# RGB_LED_1_4.net
KiCad netlist of a schematic drawn in EAGLE
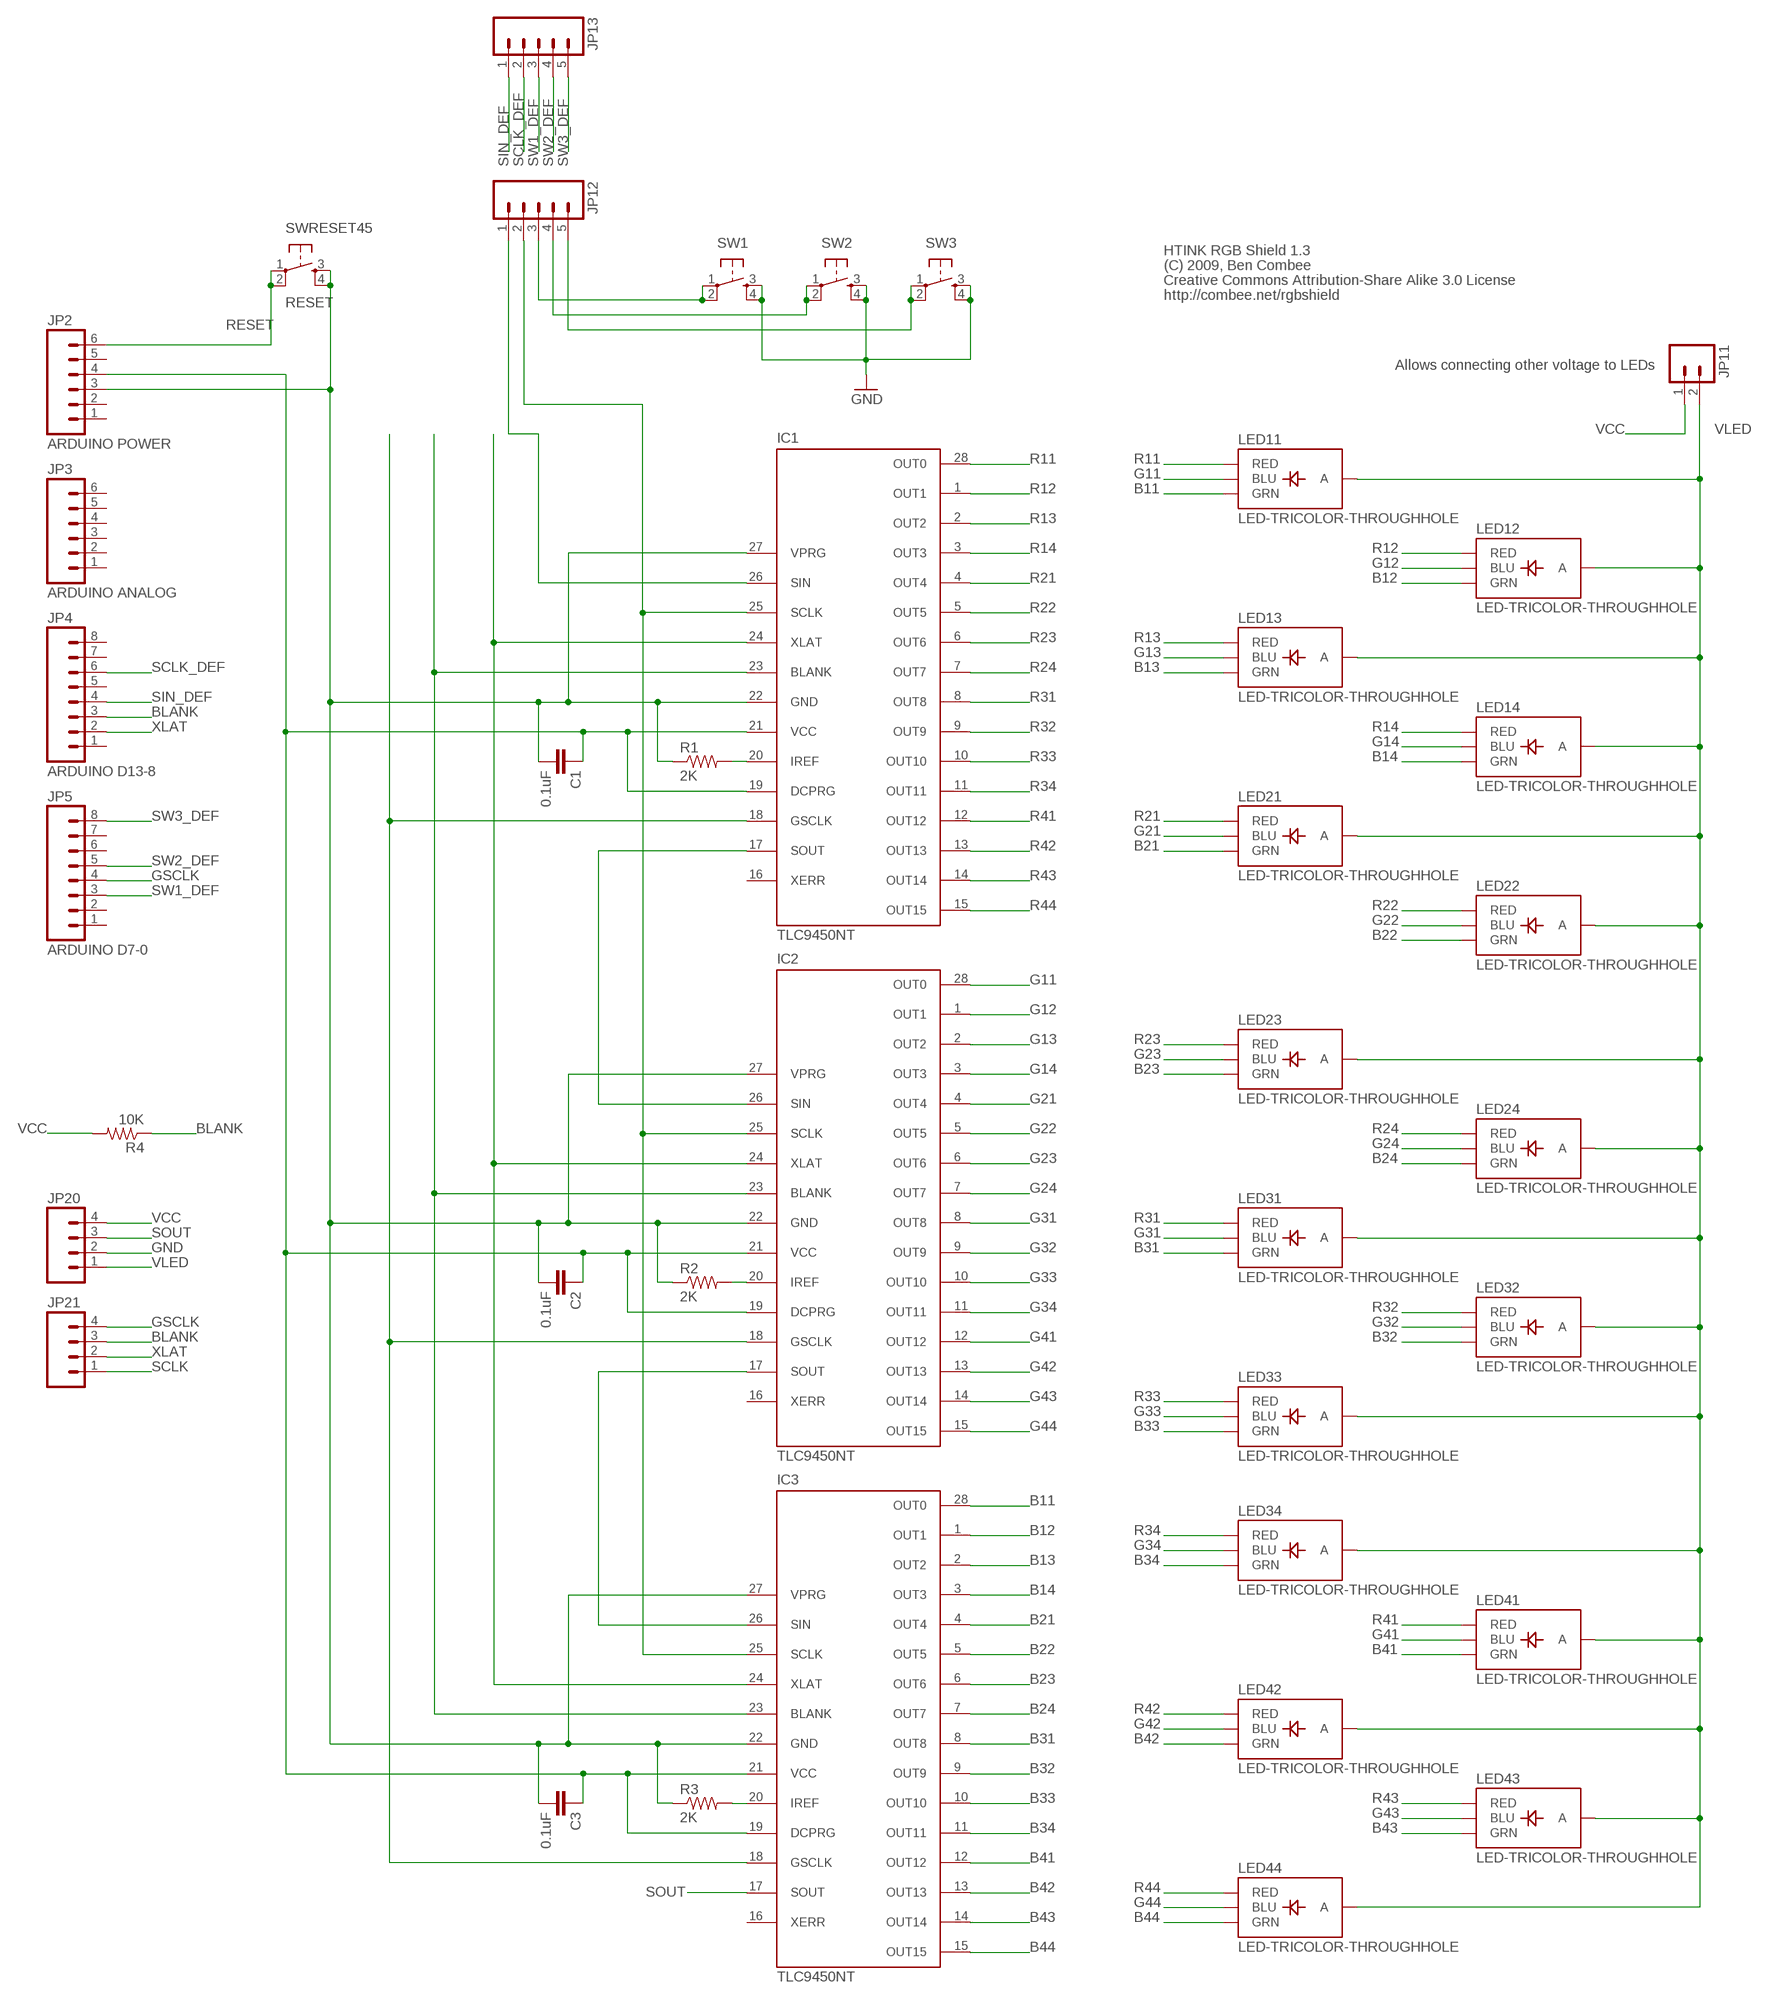
[diagram p0: schematic, sheet 1]

(export (version "E")
  (design (tool "Eeschema 10.0.6"))
  (components
    (comp (ref "C1")
      (value "0.1uF")
      (footprint "eagle-import:CAP-PTH-SMALL")
      (libsource (lib "eagle-import") (part "CAPPTH"))
    )
    (comp (ref "C2")
      (value "0.1uF")
      (footprint "eagle-import:CAP-PTH-SMALL")
      (libsource (lib "eagle-import") (part "CAPPTH"))
    )
    (comp (ref "C3")
      (value "0.1uF")
      (footprint "eagle-import:CAP-PTH-SMALL")
      (libsource (lib "eagle-import") (part "CAPPTH"))
    )
    (comp (ref "IC1")
      (value "TLC9450NT")
      (footprint "eagle-import:DIL28-3")
      (libsource (lib "eagle-import") (part "TLC9450NT"))
    )
    (comp (ref "IC2")
      (value "TLC9450NT")
      (footprint "eagle-import:DIL28-3")
      (libsource (lib "eagle-import") (part "TLC9450NT"))
    )
    (comp (ref "IC3")
      (value "TLC9450NT")
      (footprint "eagle-import:DIL28-3")
      (libsource (lib "eagle-import") (part "TLC9450NT"))
    )
    (comp (ref "JP2")
      (value "ARDUINO POWER")
      (footprint "eagle-import:1X06_LOCK")
      (libsource (lib "eagle-import") (part "M06LOCK"))
    )
    (comp (ref "JP3")
      (value "ARDUINO ANALOG")
      (footprint "eagle-import:1X06_LOCK")
      (libsource (lib "eagle-import") (part "M06LOCK"))
    )
    (comp (ref "JP4")
      (value "ARDUINO D13-8")
      (footprint "eagle-import:1X08_LOCK")
      (libsource (lib "eagle-import") (part "M08LOCK"))
    )
    (comp (ref "JP5")
      (value "ARDUINO D7-0")
      (footprint "eagle-import:1X08_LOCK")
      (libsource (lib "eagle-import") (part "M08LOCK"))
    )
    (comp (ref "JP11")
      (value "M02LOCK")
      (footprint "eagle-import:1X02_LOCK")
      (libsource (lib "eagle-import") (part "M02LOCK"))
    )
    (comp (ref "JP12")
      (value "M05LOCK")
      (footprint "eagle-import:1X05_LOCK")
      (libsource (lib "eagle-import") (part "M05LOCK"))
    )
    (comp (ref "JP13")
      (value "M05LOCK")
      (footprint "eagle-import:1X05_LOCK")
      (libsource (lib "eagle-import") (part "M05LOCK"))
    )
    (comp (ref "JP20")
      (value "M04LOCK")
      (footprint "eagle-import:1X04_LOCK")
      (libsource (lib "eagle-import") (part "M04LOCK"))
    )
    (comp (ref "JP21")
      (value "M04LOCK")
      (footprint "eagle-import:1X04_LOCK")
      (libsource (lib "eagle-import") (part "M04LOCK"))
    )
    (comp (ref "LED11")
      (value "LED-TRICOLOR-THROUGHHOLE")
      (footprint "eagle-import:LED-TRICOLOR-THROUGHHOLE")
      (libsource (lib "eagle-import") (part "LED-TRICOLOR-THROUGHHOLE"))
    )
    (comp (ref "LED12")
      (value "LED-TRICOLOR-THROUGHHOLE")
      (footprint "eagle-import:LED-TRICOLOR-THROUGHHOLE")
      (libsource (lib "eagle-import") (part "LED-TRICOLOR-THROUGHHOLE"))
    )
    (comp (ref "LED13")
      (value "LED-TRICOLOR-THROUGHHOLE")
      (footprint "eagle-import:LED-TRICOLOR-THROUGHHOLE")
      (libsource (lib "eagle-import") (part "LED-TRICOLOR-THROUGHHOLE"))
    )
    (comp (ref "LED14")
      (value "LED-TRICOLOR-THROUGHHOLE")
      (footprint "eagle-import:LED-TRICOLOR-THROUGHHOLE")
      (libsource (lib "eagle-import") (part "LED-TRICOLOR-THROUGHHOLE"))
    )
    (comp (ref "LED21")
      (value "LED-TRICOLOR-THROUGHHOLE")
      (footprint "eagle-import:LED-TRICOLOR-THROUGHHOLE")
      (libsource (lib "eagle-import") (part "LED-TRICOLOR-THROUGHHOLE"))
    )
    (comp (ref "LED22")
      (value "LED-TRICOLOR-THROUGHHOLE")
      (footprint "eagle-import:LED-TRICOLOR-THROUGHHOLE")
      (libsource (lib "eagle-import") (part "LED-TRICOLOR-THROUGHHOLE"))
    )
    (comp (ref "LED23")
      (value "LED-TRICOLOR-THROUGHHOLE")
      (footprint "eagle-import:LED-TRICOLOR-THROUGHHOLE")
      (libsource (lib "eagle-import") (part "LED-TRICOLOR-THROUGHHOLE"))
    )
    (comp (ref "LED24")
      (value "LED-TRICOLOR-THROUGHHOLE")
      (footprint "eagle-import:LED-TRICOLOR-THROUGHHOLE")
      (libsource (lib "eagle-import") (part "LED-TRICOLOR-THROUGHHOLE"))
    )
    (comp (ref "LED31")
      (value "LED-TRICOLOR-THROUGHHOLE")
      (footprint "eagle-import:LED-TRICOLOR-THROUGHHOLE")
      (libsource (lib "eagle-import") (part "LED-TRICOLOR-THROUGHHOLE"))
    )
    (comp (ref "LED32")
      (value "LED-TRICOLOR-THROUGHHOLE")
      (footprint "eagle-import:LED-TRICOLOR-THROUGHHOLE")
      (libsource (lib "eagle-import") (part "LED-TRICOLOR-THROUGHHOLE"))
    )
    (comp (ref "LED33")
      (value "LED-TRICOLOR-THROUGHHOLE")
      (footprint "eagle-import:LED-TRICOLOR-THROUGHHOLE")
      (libsource (lib "eagle-import") (part "LED-TRICOLOR-THROUGHHOLE"))
    )
    (comp (ref "LED34")
      (value "LED-TRICOLOR-THROUGHHOLE")
      (footprint "eagle-import:LED-TRICOLOR-THROUGHHOLE")
      (libsource (lib "eagle-import") (part "LED-TRICOLOR-THROUGHHOLE"))
    )
    (comp (ref "LED41")
      (value "LED-TRICOLOR-THROUGHHOLE")
      (footprint "eagle-import:LED-TRICOLOR-THROUGHHOLE")
      (libsource (lib "eagle-import") (part "LED-TRICOLOR-THROUGHHOLE"))
    )
    (comp (ref "LED42")
      (value "LED-TRICOLOR-THROUGHHOLE")
      (footprint "eagle-import:LED-TRICOLOR-THROUGHHOLE")
      (libsource (lib "eagle-import") (part "LED-TRICOLOR-THROUGHHOLE"))
    )
    (comp (ref "LED43")
      (value "LED-TRICOLOR-THROUGHHOLE")
      (footprint "eagle-import:LED-TRICOLOR-THROUGHHOLE")
      (libsource (lib "eagle-import") (part "LED-TRICOLOR-THROUGHHOLE"))
    )
    (comp (ref "LED44")
      (value "LED-TRICOLOR-THROUGHHOLE")
      (footprint "eagle-import:LED-TRICOLOR-THROUGHHOLE")
      (libsource (lib "eagle-import") (part "LED-TRICOLOR-THROUGHHOLE"))
    )
    (comp (ref "R1")
      (value "2K")
      (footprint "eagle-import:0309_12")
      (libsource (lib "eagle-import") (part "R-US_0309/12"))
    )
    (comp (ref "R2")
      (value "2K")
      (footprint "eagle-import:0309_12")
      (libsource (lib "eagle-import") (part "R-US_0309/12"))
    )
    (comp (ref "R3")
      (value "2K")
      (footprint "eagle-import:0309_12")
      (libsource (lib "eagle-import") (part "R-US_0309/12"))
    )
    (comp (ref "R4")
      (value "10K")
      (footprint "eagle-import:0309_12")
      (libsource (lib "eagle-import") (part "R-US_0309/12"))
    )
    (comp (ref "SW1")
      (value "TAC_SWITCHPTH")
      (footprint "eagle-import:TACTILE-PTH")
      (libsource (lib "eagle-import") (part "TAC_SWITCHPTH"))
    )
    (comp (ref "SW2")
      (value "TAC_SWITCHPTH")
      (footprint "eagle-import:TACTILE-PTH")
      (libsource (lib "eagle-import") (part "TAC_SWITCHPTH"))
    )
    (comp (ref "SW3")
      (value "TAC_SWITCHPTH")
      (footprint "eagle-import:TACTILE-PTH")
      (libsource (lib "eagle-import") (part "TAC_SWITCHPTH"))
    )
    (comp (ref "SWRESET45")
      (value "RESET")
      (footprint "eagle-import:TACTILE-PTH")
      (libsource (lib "eagle-import") (part "TAC_SWITCHPTH"))
    )
  )
  (nets
    (net (code "1") (name "/B11") (class "Default")
      (node (ref "IC3") (pin "28") (pinfunction "OUT0_28") (pintype "bidirectional"))
      (node (ref "LED11") (pin "GRN") (pinfunction "GRN_GRN") (pintype "bidirectional"))
    )
    (net (code "2") (name "/B12") (class "Default")
      (node (ref "IC3") (pin "1") (pinfunction "OUT1_1") (pintype "bidirectional"))
      (node (ref "LED12") (pin "GRN") (pinfunction "GRN_GRN") (pintype "bidirectional"))
    )
    (net (code "3") (name "/B13") (class "Default")
      (node (ref "IC3") (pin "2") (pinfunction "OUT2_2") (pintype "bidirectional"))
      (node (ref "LED13") (pin "GRN") (pinfunction "GRN_GRN") (pintype "bidirectional"))
    )
    (net (code "4") (name "/B14") (class "Default")
      (node (ref "IC3") (pin "3") (pinfunction "OUT3_3") (pintype "bidirectional"))
      (node (ref "LED14") (pin "GRN") (pinfunction "GRN_GRN") (pintype "bidirectional"))
    )
    (net (code "5") (name "/B21") (class "Default")
      (node (ref "IC3") (pin "4") (pinfunction "OUT4_4") (pintype "bidirectional"))
      (node (ref "LED21") (pin "GRN") (pinfunction "GRN_GRN") (pintype "bidirectional"))
    )
    (net (code "6") (name "/B22") (class "Default")
      (node (ref "IC3") (pin "5") (pinfunction "OUT5_5") (pintype "bidirectional"))
      (node (ref "LED22") (pin "GRN") (pinfunction "GRN_GRN") (pintype "bidirectional"))
    )
    (net (code "7") (name "/B23") (class "Default")
      (node (ref "IC3") (pin "6") (pinfunction "OUT6_6") (pintype "bidirectional"))
      (node (ref "LED23") (pin "GRN") (pinfunction "GRN_GRN") (pintype "bidirectional"))
    )
    (net (code "8") (name "/B24") (class "Default")
      (node (ref "IC3") (pin "7") (pinfunction "OUT7_7") (pintype "bidirectional"))
      (node (ref "LED24") (pin "GRN") (pinfunction "GRN_GRN") (pintype "bidirectional"))
    )
    (net (code "9") (name "/B31") (class "Default")
      (node (ref "IC3") (pin "8") (pinfunction "OUT8_8") (pintype "bidirectional"))
      (node (ref "LED31") (pin "GRN") (pinfunction "GRN_GRN") (pintype "bidirectional"))
    )
    (net (code "10") (name "/B32") (class "Default")
      (node (ref "IC3") (pin "9") (pinfunction "OUT9_9") (pintype "bidirectional"))
      (node (ref "LED32") (pin "GRN") (pinfunction "GRN_GRN") (pintype "bidirectional"))
    )
    (net (code "11") (name "/B33") (class "Default")
      (node (ref "IC3") (pin "10") (pinfunction "OUT10_10") (pintype "bidirectional"))
      (node (ref "LED33") (pin "GRN") (pinfunction "GRN_GRN") (pintype "bidirectional"))
    )
    (net (code "12") (name "/B34") (class "Default")
      (node (ref "IC3") (pin "11") (pinfunction "OUT11_11") (pintype "bidirectional"))
      (node (ref "LED34") (pin "GRN") (pinfunction "GRN_GRN") (pintype "bidirectional"))
    )
    (net (code "13") (name "/B41") (class "Default")
      (node (ref "IC3") (pin "12") (pinfunction "OUT12_12") (pintype "bidirectional"))
      (node (ref "LED41") (pin "GRN") (pinfunction "GRN_GRN") (pintype "bidirectional"))
    )
    (net (code "14") (name "/B42") (class "Default")
      (node (ref "IC3") (pin "13") (pinfunction "OUT13_13") (pintype "bidirectional"))
      (node (ref "LED42") (pin "GRN") (pinfunction "GRN_GRN") (pintype "bidirectional"))
    )
    (net (code "15") (name "/B43") (class "Default")
      (node (ref "IC3") (pin "14") (pinfunction "OUT14_14") (pintype "bidirectional"))
      (node (ref "LED43") (pin "GRN") (pinfunction "GRN_GRN") (pintype "bidirectional"))
    )
    (net (code "16") (name "/B44") (class "Default")
      (node (ref "IC3") (pin "15") (pinfunction "OUT15_15") (pintype "bidirectional"))
      (node (ref "LED44") (pin "GRN") (pinfunction "GRN_GRN") (pintype "bidirectional"))
    )
    (net (code "17") (name "/BLANK") (class "Default")
      (node (ref "IC1") (pin "23") (pinfunction "BLANK_23") (pintype "bidirectional"))
      (node (ref "IC2") (pin "23") (pinfunction "BLANK_23") (pintype "bidirectional"))
      (node (ref "IC3") (pin "23") (pinfunction "BLANK_23") (pintype "bidirectional"))
      (node (ref "JP21") (pin "3") (pinfunction "3_3") (pintype "passive"))
      (node (ref "JP4") (pin "3") (pinfunction "3_3") (pintype "passive"))
      (node (ref "R4") (pin "1") (pinfunction "1_1") (pintype "passive"))
    )
    (net (code "18") (name "/G11") (class "Default")
      (node (ref "IC2") (pin "28") (pinfunction "OUT0_28") (pintype "bidirectional"))
      (node (ref "LED11") (pin "BLU") (pinfunction "BLU_BLU") (pintype "bidirectional"))
    )
    (net (code "19") (name "/G12") (class "Default")
      (node (ref "IC2") (pin "1") (pinfunction "OUT1_1") (pintype "bidirectional"))
      (node (ref "LED12") (pin "BLU") (pinfunction "BLU_BLU") (pintype "bidirectional"))
    )
    (net (code "20") (name "/G13") (class "Default")
      (node (ref "IC2") (pin "2") (pinfunction "OUT2_2") (pintype "bidirectional"))
      (node (ref "LED13") (pin "BLU") (pinfunction "BLU_BLU") (pintype "bidirectional"))
    )
    (net (code "21") (name "/G14") (class "Default")
      (node (ref "IC2") (pin "3") (pinfunction "OUT3_3") (pintype "bidirectional"))
      (node (ref "LED14") (pin "BLU") (pinfunction "BLU_BLU") (pintype "bidirectional"))
    )
    (net (code "22") (name "/G21") (class "Default")
      (node (ref "IC2") (pin "4") (pinfunction "OUT4_4") (pintype "bidirectional"))
      (node (ref "LED21") (pin "BLU") (pinfunction "BLU_BLU") (pintype "bidirectional"))
    )
    (net (code "23") (name "/G22") (class "Default")
      (node (ref "IC2") (pin "5") (pinfunction "OUT5_5") (pintype "bidirectional"))
      (node (ref "LED22") (pin "BLU") (pinfunction "BLU_BLU") (pintype "bidirectional"))
    )
    (net (code "24") (name "/G23") (class "Default")
      (node (ref "IC2") (pin "6") (pinfunction "OUT6_6") (pintype "bidirectional"))
      (node (ref "LED23") (pin "BLU") (pinfunction "BLU_BLU") (pintype "bidirectional"))
    )
    (net (code "25") (name "/G24") (class "Default")
      (node (ref "IC2") (pin "7") (pinfunction "OUT7_7") (pintype "bidirectional"))
      (node (ref "LED24") (pin "BLU") (pinfunction "BLU_BLU") (pintype "bidirectional"))
    )
    (net (code "26") (name "/G31") (class "Default")
      (node (ref "IC2") (pin "8") (pinfunction "OUT8_8") (pintype "bidirectional"))
      (node (ref "LED31") (pin "BLU") (pinfunction "BLU_BLU") (pintype "bidirectional"))
    )
    (net (code "27") (name "/G32") (class "Default")
      (node (ref "IC2") (pin "9") (pinfunction "OUT9_9") (pintype "bidirectional"))
      (node (ref "LED32") (pin "BLU") (pinfunction "BLU_BLU") (pintype "bidirectional"))
    )
    (net (code "28") (name "/G33") (class "Default")
      (node (ref "IC2") (pin "10") (pinfunction "OUT10_10") (pintype "bidirectional"))
      (node (ref "LED33") (pin "BLU") (pinfunction "BLU_BLU") (pintype "bidirectional"))
    )
    (net (code "29") (name "/G34") (class "Default")
      (node (ref "IC2") (pin "11") (pinfunction "OUT11_11") (pintype "bidirectional"))
      (node (ref "LED34") (pin "BLU") (pinfunction "BLU_BLU") (pintype "bidirectional"))
    )
    (net (code "30") (name "/G41") (class "Default")
      (node (ref "IC2") (pin "12") (pinfunction "OUT12_12") (pintype "bidirectional"))
      (node (ref "LED41") (pin "BLU") (pinfunction "BLU_BLU") (pintype "bidirectional"))
    )
    (net (code "31") (name "/G42") (class "Default")
      (node (ref "IC2") (pin "13") (pinfunction "OUT13_13") (pintype "bidirectional"))
      (node (ref "LED42") (pin "BLU") (pinfunction "BLU_BLU") (pintype "bidirectional"))
    )
    (net (code "32") (name "/G43") (class "Default")
      (node (ref "IC2") (pin "14") (pinfunction "OUT14_14") (pintype "bidirectional"))
      (node (ref "LED43") (pin "BLU") (pinfunction "BLU_BLU") (pintype "bidirectional"))
    )
    (net (code "33") (name "/G44") (class "Default")
      (node (ref "IC2") (pin "15") (pinfunction "OUT15_15") (pintype "bidirectional"))
      (node (ref "LED44") (pin "BLU") (pinfunction "BLU_BLU") (pintype "bidirectional"))
    )
    (net (code "34") (name "/GSCLK") (class "Default")
      (node (ref "IC1") (pin "18") (pinfunction "GSCLK_18") (pintype "bidirectional"))
      (node (ref "IC2") (pin "18") (pinfunction "GSCLK_18") (pintype "bidirectional"))
      (node (ref "IC3") (pin "18") (pinfunction "GSCLK_18") (pintype "bidirectional"))
      (node (ref "JP21") (pin "4") (pinfunction "4_4") (pintype "passive"))
      (node (ref "JP5") (pin "4") (pinfunction "4_4") (pintype "passive"))
    )
    (net (code "35") (name "/R11") (class "Default")
      (node (ref "IC1") (pin "28") (pinfunction "OUT0_28") (pintype "bidirectional"))
      (node (ref "LED11") (pin "RED") (pinfunction "RED_RED") (pintype "bidirectional"))
    )
    (net (code "36") (name "/R12") (class "Default")
      (node (ref "IC1") (pin "1") (pinfunction "OUT1_1") (pintype "bidirectional"))
      (node (ref "LED12") (pin "RED") (pinfunction "RED_RED") (pintype "bidirectional"))
    )
    (net (code "37") (name "/R13") (class "Default")
      (node (ref "IC1") (pin "2") (pinfunction "OUT2_2") (pintype "bidirectional"))
      (node (ref "LED13") (pin "RED") (pinfunction "RED_RED") (pintype "bidirectional"))
    )
    (net (code "38") (name "/R14") (class "Default")
      (node (ref "IC1") (pin "3") (pinfunction "OUT3_3") (pintype "bidirectional"))
      (node (ref "LED14") (pin "RED") (pinfunction "RED_RED") (pintype "bidirectional"))
    )
    (net (code "39") (name "/R21") (class "Default")
      (node (ref "IC1") (pin "4") (pinfunction "OUT4_4") (pintype "bidirectional"))
      (node (ref "LED21") (pin "RED") (pinfunction "RED_RED") (pintype "bidirectional"))
    )
    (net (code "40") (name "/R22") (class "Default")
      (node (ref "IC1") (pin "5") (pinfunction "OUT5_5") (pintype "bidirectional"))
      (node (ref "LED22") (pin "RED") (pinfunction "RED_RED") (pintype "bidirectional"))
    )
    (net (code "41") (name "/R23") (class "Default")
      (node (ref "IC1") (pin "6") (pinfunction "OUT6_6") (pintype "bidirectional"))
      (node (ref "LED23") (pin "RED") (pinfunction "RED_RED") (pintype "bidirectional"))
    )
    (net (code "42") (name "/R24") (class "Default")
      (node (ref "IC1") (pin "7") (pinfunction "OUT7_7") (pintype "bidirectional"))
      (node (ref "LED24") (pin "RED") (pinfunction "RED_RED") (pintype "bidirectional"))
    )
    (net (code "43") (name "/R31") (class "Default")
      (node (ref "IC1") (pin "8") (pinfunction "OUT8_8") (pintype "bidirectional"))
      (node (ref "LED31") (pin "RED") (pinfunction "RED_RED") (pintype "bidirectional"))
    )
    (net (code "44") (name "/R32") (class "Default")
      (node (ref "IC1") (pin "9") (pinfunction "OUT9_9") (pintype "bidirectional"))
      (node (ref "LED32") (pin "RED") (pinfunction "RED_RED") (pintype "bidirectional"))
    )
    (net (code "45") (name "/R33") (class "Default")
      (node (ref "IC1") (pin "10") (pinfunction "OUT10_10") (pintype "bidirectional"))
      (node (ref "LED33") (pin "RED") (pinfunction "RED_RED") (pintype "bidirectional"))
    )
    (net (code "46") (name "/R34") (class "Default")
      (node (ref "IC1") (pin "11") (pinfunction "OUT11_11") (pintype "bidirectional"))
      (node (ref "LED34") (pin "RED") (pinfunction "RED_RED") (pintype "bidirectional"))
    )
    (net (code "47") (name "/R41") (class "Default")
      (node (ref "IC1") (pin "12") (pinfunction "OUT12_12") (pintype "bidirectional"))
      (node (ref "LED41") (pin "RED") (pinfunction "RED_RED") (pintype "bidirectional"))
    )
    (net (code "48") (name "/R42") (class "Default")
      (node (ref "IC1") (pin "13") (pinfunction "OUT13_13") (pintype "bidirectional"))
      (node (ref "LED42") (pin "RED") (pinfunction "RED_RED") (pintype "bidirectional"))
    )
    (net (code "49") (name "/R43") (class "Default")
      (node (ref "IC1") (pin "14") (pinfunction "OUT14_14") (pintype "bidirectional"))
      (node (ref "LED43") (pin "RED") (pinfunction "RED_RED") (pintype "bidirectional"))
    )
    (net (code "50") (name "/R44") (class "Default")
      (node (ref "IC1") (pin "15") (pinfunction "OUT15_15") (pintype "bidirectional"))
      (node (ref "LED44") (pin "RED") (pinfunction "RED_RED") (pintype "bidirectional"))
    )
    (net (code "51") (name "/RESET") (class "Default")
      (node (ref "JP2") (pin "6") (pinfunction "6_6") (pintype "passive"))
      (node (ref "SWRESET45") (pin "1") (pinfunction "1_1") (pintype "passive"))
      (node (ref "SWRESET45") (pin "2") (pinfunction "2_2") (pintype "passive"))
    )
    (net (code "52") (name "/SCLK") (class "Default")
      (node (ref "IC1") (pin "25") (pinfunction "SCLK_25") (pintype "bidirectional"))
      (node (ref "IC2") (pin "25") (pinfunction "SCLK_25") (pintype "bidirectional"))
      (node (ref "IC3") (pin "25") (pinfunction "SCLK_25") (pintype "bidirectional"))
      (node (ref "JP12") (pin "2") (pinfunction "2_2") (pintype "passive"))
      (node (ref "JP21") (pin "1") (pinfunction "1_1") (pintype "passive"))
    )
    (net (code "53") (name "/SCLK_DEF") (class "Default")
      (node (ref "JP13") (pin "2") (pinfunction "2_2") (pintype "passive"))
      (node (ref "JP4") (pin "6") (pinfunction "6_6") (pintype "passive"))
    )
    (net (code "54") (name "/SIN") (class "Default")
      (node (ref "IC1") (pin "26") (pinfunction "SIN_26") (pintype "bidirectional"))
      (node (ref "JP12") (pin "1") (pinfunction "1_1") (pintype "passive"))
    )
    (net (code "55") (name "/SIN_DEF") (class "Default")
      (node (ref "JP13") (pin "1") (pinfunction "1_1") (pintype "passive"))
      (node (ref "JP4") (pin "4") (pinfunction "4_4") (pintype "passive"))
    )
    (net (code "56") (name "/SOUT") (class "Default")
      (node (ref "IC3") (pin "17") (pinfunction "SOUT_17") (pintype "bidirectional"))
      (node (ref "JP20") (pin "3") (pinfunction "3_3") (pintype "passive"))
    )
    (net (code "57") (name "/SW1_DEF") (class "Default")
      (node (ref "JP13") (pin "3") (pinfunction "3_3") (pintype "passive"))
      (node (ref "JP5") (pin "3") (pinfunction "3_3") (pintype "passive"))
    )
    (net (code "58") (name "/SW2_DEF") (class "Default")
      (node (ref "JP13") (pin "4") (pinfunction "4_4") (pintype "passive"))
      (node (ref "JP5") (pin "5") (pinfunction "5_5") (pintype "passive"))
    )
    (net (code "59") (name "/SW3_DEF") (class "Default")
      (node (ref "JP13") (pin "5") (pinfunction "5_5") (pintype "passive"))
      (node (ref "JP5") (pin "8") (pinfunction "8_8") (pintype "passive"))
    )
    (net (code "60") (name "/VCC") (class "Default")
      (node (ref "C1") (pin "1") (pinfunction "1_1") (pintype "passive"))
      (node (ref "C2") (pin "1") (pinfunction "1_1") (pintype "passive"))
      (node (ref "C3") (pin "1") (pinfunction "1_1") (pintype "passive"))
      (node (ref "IC1") (pin "19") (pinfunction "DCPRG_19") (pintype "bidirectional"))
      (node (ref "IC1") (pin "21") (pinfunction "VCC_21") (pintype "bidirectional"))
      (node (ref "IC2") (pin "19") (pinfunction "DCPRG_19") (pintype "bidirectional"))
      (node (ref "IC2") (pin "21") (pinfunction "VCC_21") (pintype "bidirectional"))
      (node (ref "IC3") (pin "19") (pinfunction "DCPRG_19") (pintype "bidirectional"))
      (node (ref "IC3") (pin "21") (pinfunction "VCC_21") (pintype "bidirectional"))
      (node (ref "JP11") (pin "1") (pinfunction "1_1") (pintype "passive"))
      (node (ref "JP2") (pin "4") (pinfunction "4_4") (pintype "passive"))
      (node (ref "JP20") (pin "4") (pinfunction "4_4") (pintype "passive"))
      (node (ref "R4") (pin "2") (pinfunction "2_2") (pintype "passive"))
    )
    (net (code "61") (name "/VLED") (class "Default")
      (node (ref "JP11") (pin "2") (pinfunction "2_2") (pintype "passive"))
      (node (ref "JP20") (pin "1") (pinfunction "1_1") (pintype "passive"))
      (node (ref "LED11") (pin "GND") (pinfunction "A_GND") (pintype "bidirectional"))
      (node (ref "LED12") (pin "GND") (pinfunction "A_GND") (pintype "bidirectional"))
      (node (ref "LED13") (pin "GND") (pinfunction "A_GND") (pintype "bidirectional"))
      (node (ref "LED14") (pin "GND") (pinfunction "A_GND") (pintype "bidirectional"))
      (node (ref "LED21") (pin "GND") (pinfunction "A_GND") (pintype "bidirectional"))
      (node (ref "LED22") (pin "GND") (pinfunction "A_GND") (pintype "bidirectional"))
      (node (ref "LED23") (pin "GND") (pinfunction "A_GND") (pintype "bidirectional"))
      (node (ref "LED24") (pin "GND") (pinfunction "A_GND") (pintype "bidirectional"))
      (node (ref "LED31") (pin "GND") (pinfunction "A_GND") (pintype "bidirectional"))
      (node (ref "LED32") (pin "GND") (pinfunction "A_GND") (pintype "bidirectional"))
      (node (ref "LED33") (pin "GND") (pinfunction "A_GND") (pintype "bidirectional"))
      (node (ref "LED34") (pin "GND") (pinfunction "A_GND") (pintype "bidirectional"))
      (node (ref "LED41") (pin "GND") (pinfunction "A_GND") (pintype "bidirectional"))
      (node (ref "LED42") (pin "GND") (pinfunction "A_GND") (pintype "bidirectional"))
      (node (ref "LED43") (pin "GND") (pinfunction "A_GND") (pintype "bidirectional"))
      (node (ref "LED44") (pin "GND") (pinfunction "A_GND") (pintype "bidirectional"))
    )
    (net (code "62") (name "/XLAT") (class "Default")
      (node (ref "IC1") (pin "24") (pinfunction "XLAT_24") (pintype "bidirectional"))
      (node (ref "IC2") (pin "24") (pinfunction "XLAT_24") (pintype "bidirectional"))
      (node (ref "IC3") (pin "24") (pinfunction "XLAT_24") (pintype "bidirectional"))
      (node (ref "JP21") (pin "2") (pinfunction "2_2") (pintype "passive"))
      (node (ref "JP4") (pin "2") (pinfunction "2_2") (pintype "passive"))
    )
    (net (code "63") (name "GND") (class "Default")
      (node (ref "C1") (pin "2") (pinfunction "2_2") (pintype "passive"))
      (node (ref "C2") (pin "2") (pinfunction "2_2") (pintype "passive"))
      (node (ref "C3") (pin "2") (pinfunction "2_2") (pintype "passive"))
      (node (ref "IC1") (pin "22") (pinfunction "GND_22") (pintype "bidirectional"))
      (node (ref "IC1") (pin "27") (pinfunction "VPRG_27") (pintype "bidirectional"))
      (node (ref "IC2") (pin "22") (pinfunction "GND_22") (pintype "bidirectional"))
      (node (ref "IC2") (pin "27") (pinfunction "VPRG_27") (pintype "bidirectional"))
      (node (ref "IC3") (pin "22") (pinfunction "GND_22") (pintype "bidirectional"))
      (node (ref "IC3") (pin "27") (pinfunction "VPRG_27") (pintype "bidirectional"))
      (node (ref "JP2") (pin "3") (pinfunction "3_3") (pintype "passive"))
      (node (ref "JP20") (pin "2") (pinfunction "2_2") (pintype "passive"))
      (node (ref "R1") (pin "1") (pinfunction "1_1") (pintype "passive"))
      (node (ref "R2") (pin "1") (pinfunction "1_1") (pintype "passive"))
      (node (ref "R3") (pin "1") (pinfunction "1_1") (pintype "passive"))
      (node (ref "SW1") (pin "3") (pinfunction "3_3") (pintype "passive"))
      (node (ref "SW1") (pin "4") (pinfunction "4_4") (pintype "passive"))
      (node (ref "SW2") (pin "3") (pinfunction "3_3") (pintype "passive"))
      (node (ref "SW2") (pin "4") (pinfunction "4_4") (pintype "passive"))
      (node (ref "SW3") (pin "3") (pinfunction "3_3") (pintype "passive"))
      (node (ref "SW3") (pin "4") (pinfunction "4_4") (pintype "passive"))
      (node (ref "SWRESET45") (pin "3") (pinfunction "3_3") (pintype "passive"))
      (node (ref "SWRESET45") (pin "4") (pinfunction "4_4") (pintype "passive"))
    )
    (net (code "64") (name "Net-(IC1-IREF)") (class "Default")
      (node (ref "IC1") (pin "20") (pinfunction "IREF_20") (pintype "bidirectional"))
      (node (ref "R1") (pin "2") (pinfunction "2_2") (pintype "passive"))
    )
    (net (code "65") (name "Net-(IC1-SOUT)") (class "Default")
      (node (ref "IC1") (pin "17") (pinfunction "SOUT_17") (pintype "bidirectional"))
      (node (ref "IC2") (pin "26") (pinfunction "SIN_26") (pintype "bidirectional"))
    )
    (net (code "66") (name "Net-(IC2-IREF)") (class "Default")
      (node (ref "IC2") (pin "20") (pinfunction "IREF_20") (pintype "bidirectional"))
      (node (ref "R2") (pin "2") (pinfunction "2_2") (pintype "passive"))
    )
    (net (code "67") (name "Net-(IC2-SOUT)") (class "Default")
      (node (ref "IC2") (pin "17") (pinfunction "SOUT_17") (pintype "bidirectional"))
      (node (ref "IC3") (pin "26") (pinfunction "SIN_26") (pintype "bidirectional"))
    )
    (net (code "68") (name "Net-(IC3-IREF)") (class "Default")
      (node (ref "IC3") (pin "20") (pinfunction "IREF_20") (pintype "bidirectional"))
      (node (ref "R3") (pin "2") (pinfunction "2_2") (pintype "passive"))
    )
    (net (code "69") (name "Net-(JP12-Pad3)") (class "Default")
      (node (ref "JP12") (pin "3") (pinfunction "3_3") (pintype "passive"))
      (node (ref "SW1") (pin "1") (pinfunction "1_1") (pintype "passive"))
      (node (ref "SW1") (pin "2") (pinfunction "2_2") (pintype "passive"))
    )
    (net (code "70") (name "Net-(JP12-Pad4)") (class "Default")
      (node (ref "JP12") (pin "4") (pinfunction "4_4") (pintype "passive"))
      (node (ref "SW2") (pin "1") (pinfunction "1_1") (pintype "passive"))
      (node (ref "SW2") (pin "2") (pinfunction "2_2") (pintype "passive"))
    )
    (net (code "71") (name "Net-(JP12-Pad5)") (class "Default")
      (node (ref "JP12") (pin "5") (pinfunction "5_5") (pintype "passive"))
      (node (ref "SW3") (pin "1") (pinfunction "1_1") (pintype "passive"))
      (node (ref "SW3") (pin "2") (pinfunction "2_2") (pintype "passive"))
    )
    (net (code "72") (name "unconnected-(IC1-XERR-Pad16)") (class "Default")
      (node (ref "IC1") (pin "16") (pinfunction "XERR_16") (pintype "bidirectional"))
    )
    (net (code "73") (name "unconnected-(IC2-XERR-Pad16)") (class "Default")
      (node (ref "IC2") (pin "16") (pinfunction "XERR_16") (pintype "bidirectional"))
    )
    (net (code "74") (name "unconnected-(IC3-XERR-Pad16)") (class "Default")
      (node (ref "IC3") (pin "16") (pinfunction "XERR_16") (pintype "bidirectional"))
    )
    (net (code "75") (name "unconnected-(JP2-Pad1)") (class "Default")
      (node (ref "JP2") (pin "1") (pinfunction "1_1") (pintype "passive"))
    )
    (net (code "76") (name "unconnected-(JP2-Pad2)") (class "Default")
      (node (ref "JP2") (pin "2") (pinfunction "2_2") (pintype "passive"))
    )
    (net (code "77") (name "unconnected-(JP2-Pad5)") (class "Default")
      (node (ref "JP2") (pin "5") (pinfunction "5_5") (pintype "passive"))
    )
    (net (code "78") (name "unconnected-(JP3-Pad1)") (class "Default")
      (node (ref "JP3") (pin "1") (pinfunction "1_1") (pintype "passive"))
    )
    (net (code "79") (name "unconnected-(JP3-Pad2)") (class "Default")
      (node (ref "JP3") (pin "2") (pinfunction "2_2") (pintype "passive"))
    )
    (net (code "80") (name "unconnected-(JP3-Pad3)") (class "Default")
      (node (ref "JP3") (pin "3") (pinfunction "3_3") (pintype "passive"))
    )
    (net (code "81") (name "unconnected-(JP3-Pad4)") (class "Default")
      (node (ref "JP3") (pin "4") (pinfunction "4_4") (pintype "passive"))
    )
    (net (code "82") (name "unconnected-(JP3-Pad5)") (class "Default")
      (node (ref "JP3") (pin "5") (pinfunction "5_5") (pintype "passive"))
    )
    (net (code "83") (name "unconnected-(JP3-Pad6)") (class "Default")
      (node (ref "JP3") (pin "6") (pinfunction "6_6") (pintype "passive"))
    )
    (net (code "84") (name "unconnected-(JP4-Pad1)") (class "Default")
      (node (ref "JP4") (pin "1") (pinfunction "1_1") (pintype "passive"))
    )
    (net (code "85") (name "unconnected-(JP4-Pad5)") (class "Default")
      (node (ref "JP4") (pin "5") (pinfunction "5_5") (pintype "passive"))
    )
    (net (code "86") (name "unconnected-(JP4-Pad7)") (class "Default")
      (node (ref "JP4") (pin "7") (pinfunction "7_7") (pintype "passive"))
    )
    (net (code "87") (name "unconnected-(JP4-Pad8)") (class "Default")
      (node (ref "JP4") (pin "8") (pinfunction "8_8") (pintype "passive"))
    )
    (net (code "88") (name "unconnected-(JP5-Pad1)") (class "Default")
      (node (ref "JP5") (pin "1") (pinfunction "1_1") (pintype "passive"))
    )
    (net (code "89") (name "unconnected-(JP5-Pad2)") (class "Default")
      (node (ref "JP5") (pin "2") (pinfunction "2_2") (pintype "passive"))
    )
    (net (code "90") (name "unconnected-(JP5-Pad6)") (class "Default")
      (node (ref "JP5") (pin "6") (pinfunction "6_6") (pintype "passive"))
    )
    (net (code "91") (name "unconnected-(JP5-Pad7)") (class "Default")
      (node (ref "JP5") (pin "7") (pinfunction "7_7") (pintype "passive"))
    )
  )
)
